# HRT_D_ER100_V1_0.net
KiCad netlist of a schematic drawn in Altium Designer
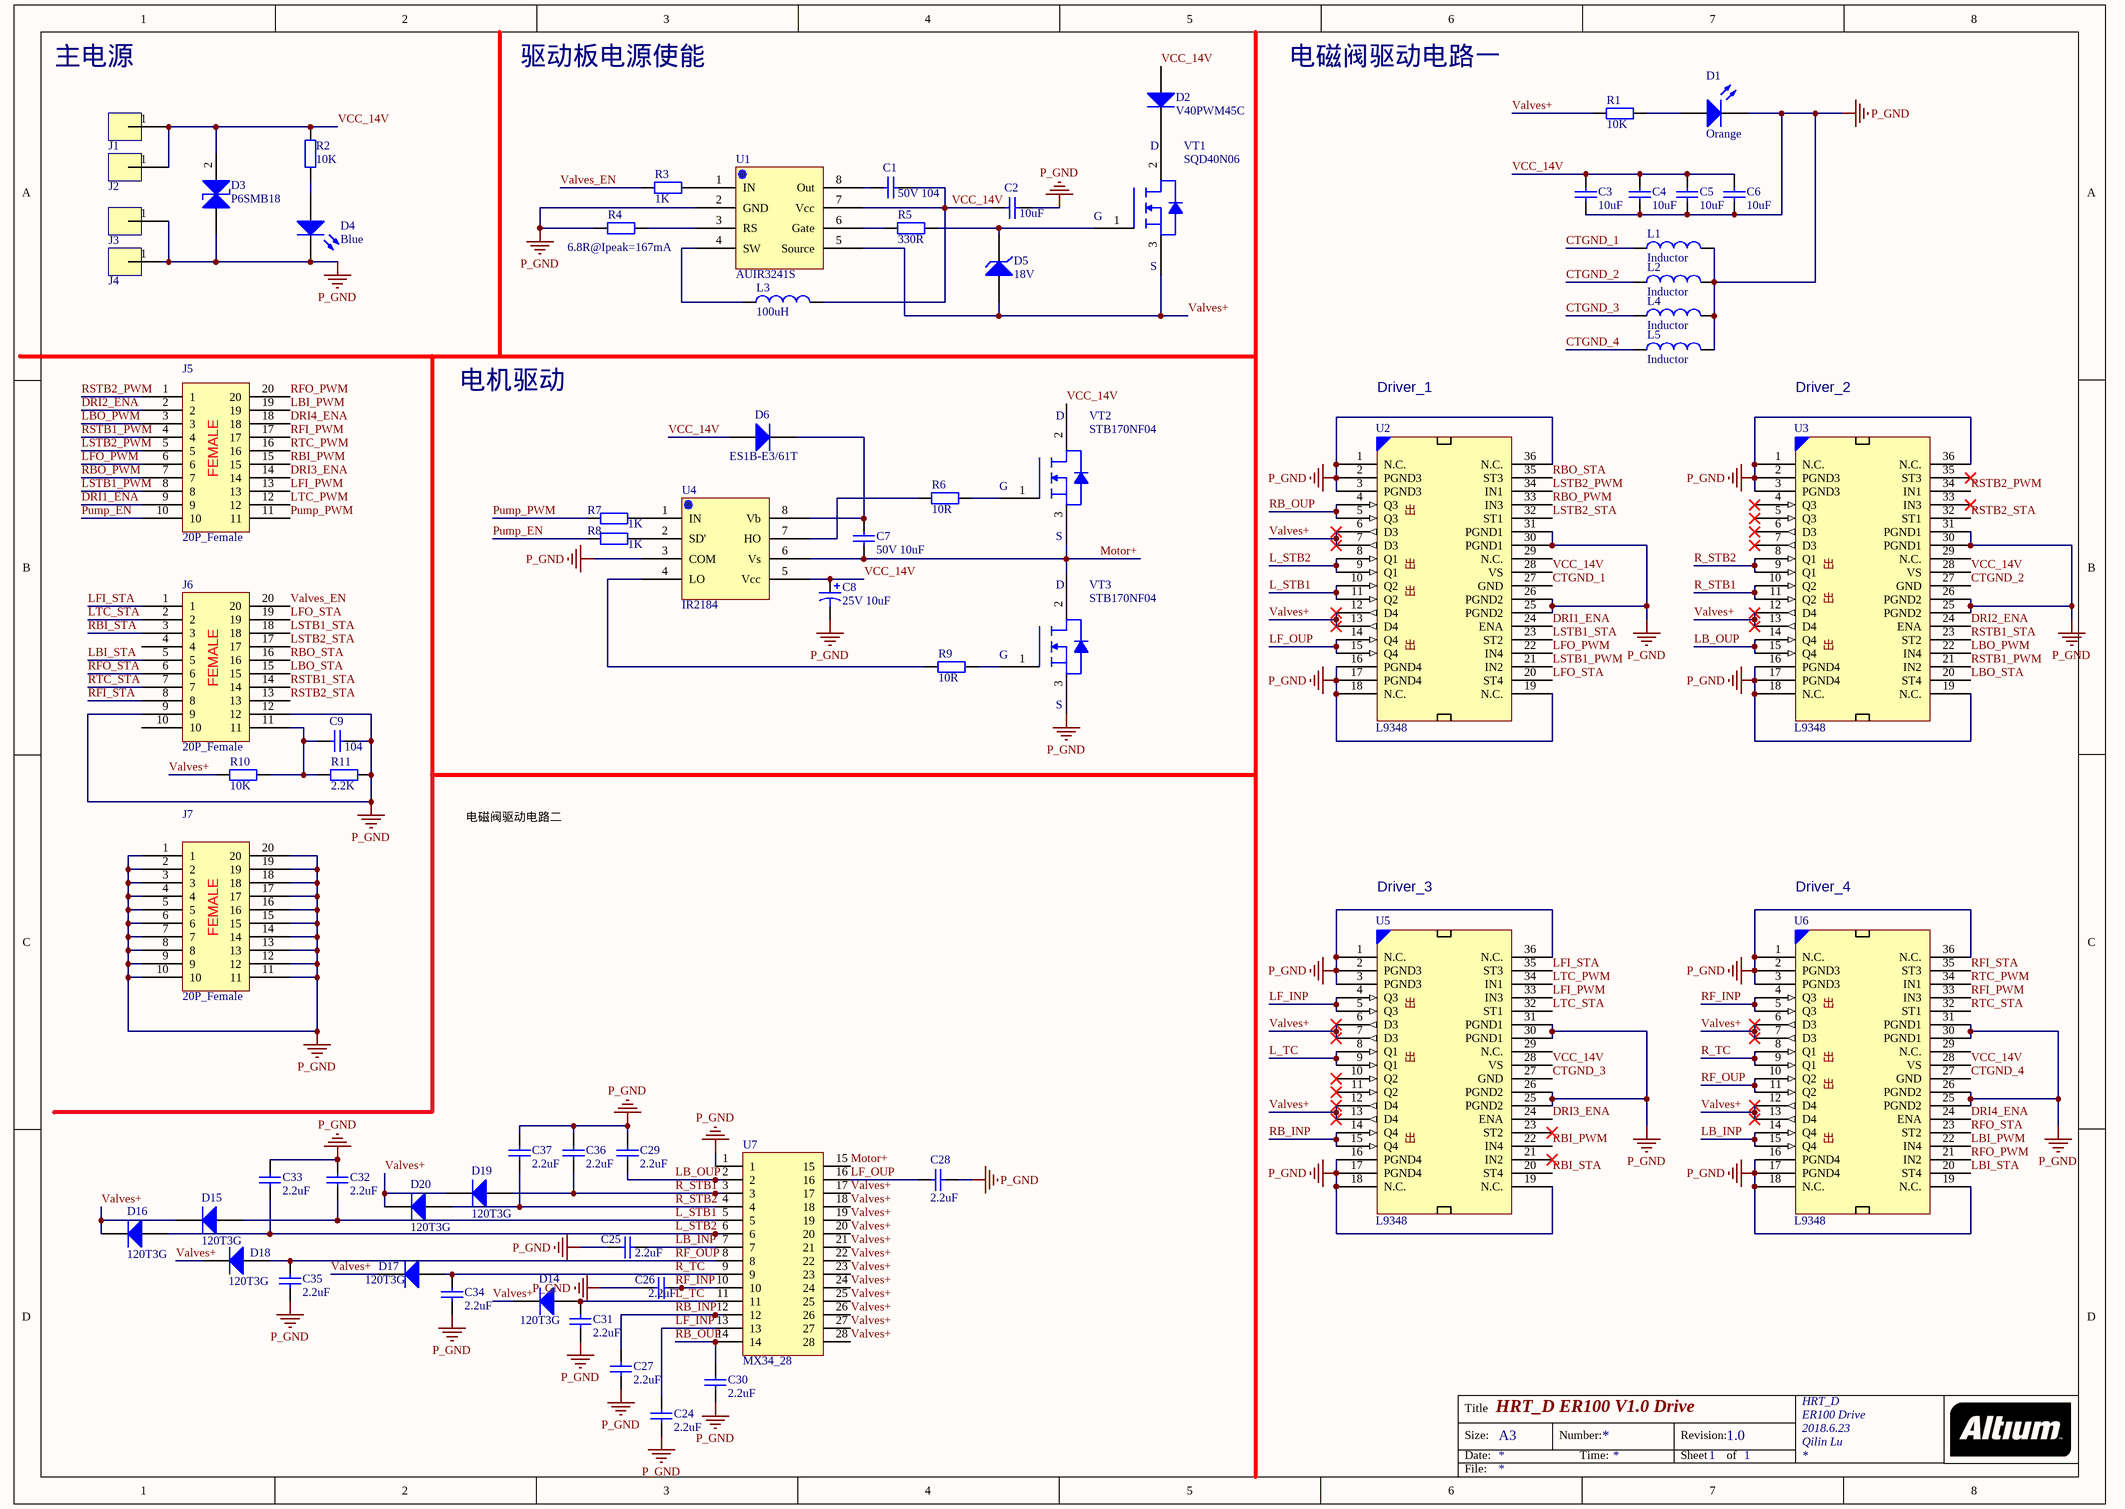
[diagram p0: HRT_D ER100 V1.0.SchDoc]

(export (version "E")
  (design (tool "Eeschema 10.0.6"))
  (components
    (comp (ref "C1")
      (value "50V 104")
      (footprint "C 0805")
      (description "无极性电容")
      (libsource (lib "HRT_D Integrated_Library") (part "Cap"))
    )
    (comp (ref "C2")
      (value "10uF")
      (footprint "C 0805")
      (description "无极性电容")
      (libsource (lib "HRT_D Integrated_Library") (part "Cap"))
    )
    (comp (ref "C3")
      (value "10uF")
      (footprint "C 0805")
      (description "无极性电容")
      (libsource (lib "HRT_D Integrated_Library") (part "Cap"))
    )
    (comp (ref "C4")
      (value "10uF")
      (footprint "C 0805")
      (description "无极性电容")
      (libsource (lib "HRT_D Integrated_Library") (part "Cap"))
    )
    (comp (ref "C5")
      (value "10uF")
      (footprint "C 0805")
      (description "无极性电容")
      (libsource (lib "HRT_D Integrated_Library") (part "Cap"))
    )
    (comp (ref "C6")
      (value "10uF")
      (footprint "C 0805")
      (description "无极性电容")
      (libsource (lib "HRT_D Integrated_Library") (part "Cap"))
    )
    (comp (ref "C7")
      (value "50V 10uF")
      (footprint "C 0805")
      (description "无极性电容")
      (libsource (lib "HRT_D Integrated_Library") (part "Cap"))
    )
    (comp (ref "C8")
      (value "25V 10uF")
      (footprint "CP 3528B")
      (description "极性电容")
      (libsource (lib "HRT_D Integrated_Library") (part "Cap_Pol"))
    )
    (comp (ref "C9")
      (value "104")
      (footprint "C 0805")
      (description "无极性电容")
      (libsource (lib "HRT_D Integrated_Library") (part "Cap"))
    )
    (comp (ref "C24")
      (value "2.2uF")
      (footprint "C 0805")
      (description "无极性电容")
      (libsource (lib "ER100_ESC") (part "Cap"))
    )
    (comp (ref "C25")
      (value "2.2uF")
      (footprint "C 0805")
      (description "无极性电容")
      (libsource (lib "ER100_ESC") (part "Cap"))
    )
    (comp (ref "C26")
      (value "2.2uF")
      (footprint "C 0805")
      (description "无极性电容")
      (libsource (lib "ER100_ESC") (part "Cap"))
    )
    (comp (ref "C27")
      (value "2.2uF")
      (footprint "C 0805")
      (description "无极性电容")
      (libsource (lib "ER100_ESC") (part "Cap"))
    )
    (comp (ref "C28")
      (value "2.2uF")
      (footprint "C 0805")
      (description "无极性电容")
      (libsource (lib "ER100_ESC") (part "Cap"))
    )
    (comp (ref "C29")
      (value "2.2uF")
      (footprint "C 0805")
      (description "无极性电容")
      (libsource (lib "ER100_ESC") (part "Cap"))
    )
    (comp (ref "C30")
      (value "2.2uF")
      (footprint "C 0805")
      (description "无极性电容")
      (libsource (lib "ER100_ESC") (part "Cap"))
    )
    (comp (ref "C31")
      (value "2.2uF")
      (footprint "C 0805")
      (description "无极性电容")
      (libsource (lib "ER100_ESC") (part "Cap"))
    )
    (comp (ref "C32")
      (value "2.2uF")
      (footprint "C 0805")
      (description "无极性电容")
      (libsource (lib "ER100_ESC") (part "Cap"))
    )
    (comp (ref "C33")
      (value "2.2uF")
      (footprint "C 0805")
      (description "无极性电容")
      (libsource (lib "ER100_ESC") (part "Cap"))
    )
    (comp (ref "C34")
      (value "2.2uF")
      (footprint "C 0805")
      (description "无极性电容")
      (libsource (lib "ER100_ESC") (part "Cap"))
    )
    (comp (ref "C35")
      (value "2.2uF")
      (footprint "C 0805")
      (description "无极性电容")
      (libsource (lib "ER100_ESC") (part "Cap"))
    )
    (comp (ref "C36")
      (value "2.2uF")
      (footprint "C 0805")
      (description "无极性电容")
      (libsource (lib "ER100_ESC") (part "Cap"))
    )
    (comp (ref "C37")
      (value "2.2uF")
      (footprint "C 0805")
      (description "无极性电容")
      (libsource (lib "ER100_ESC") (part "Cap"))
    )
    (comp (ref "D1")
      (value "Orange")
      (footprint "LED_0805")
      (description "发光二极管")
      (libsource (lib "HRT_D Integrated_Library") (part "LED"))
    )
    (comp (ref "D2")
      (value "V40PWM45C")
      (footprint "TO252_DIO")
      (description "二极管")
      (libsource (lib "HRT_D Integrated_Library") (part "Diode"))
    )
    (comp (ref "D3")
      (value "P6SMB18")
      (footprint "DO-214AA")
      (description "BiDir TVS Diode")
      (libsource (lib "HRT_D Integrated_Library") (part "P6SMBXX"))
    )
    (comp (ref "D4")
      (value "Blue")
      (footprint "LED_0805")
      (description "发光二极管")
      (libsource (lib "HRT_D Integrated_Library") (part "LED"))
    )
    (comp (ref "D5")
      (value "18V")
      (footprint "LL34")
      (libsource (lib "HRT_D Integrated_Library") (part "Diode_Zener"))
    )
    (comp (ref "D6")
      (value "ES1B-E3/61T")
      (footprint "DO-214AC")
      (description "二极管")
      (libsource (lib "HRT_D Integrated_Library") (part "Diode"))
    )
    (comp (ref "D14")
      (value "120T3G")
      (footprint "DO-214")
      (description "二极管")
      (libsource (lib "ER100_ESC") (part "Diode"))
    )
    (comp (ref "D15")
      (value "120T3G")
      (footprint "DO-214")
      (description "二极管")
      (libsource (lib "ER100_ESC") (part "Diode"))
    )
    (comp (ref "D16")
      (value "120T3G")
      (footprint "DO-214")
      (description "二极管")
      (libsource (lib "ER100_ESC") (part "Diode"))
    )
    (comp (ref "D17")
      (value "120T3G")
      (footprint "DO-214")
      (description "二极管")
      (libsource (lib "ER100_ESC") (part "Diode"))
    )
    (comp (ref "D18")
      (value "120T3G")
      (footprint "DO-214")
      (description "二极管")
      (libsource (lib "ER100_ESC") (part "Diode"))
    )
    (comp (ref "D19")
      (value "120T3G")
      (footprint "DO-214")
      (description "二极管")
      (libsource (lib "ER100_ESC") (part "Diode"))
    )
    (comp (ref "D20")
      (value "120T3G")
      (footprint "DO-214")
      (description "二极管")
      (libsource (lib "ER100_ESC") (part "Diode"))
    )
    (comp (ref "J1")
      (value "SMT_Connector")
      (footprint "SMT_Connector")
      (description "表贴接线端")
      (libsource (lib "HRT_D Integrated_Library") (part "SMT_Connector"))
    )
    (comp (ref "J2")
      (value "SMT_Connector")
      (footprint "SMT_Connector")
      (description "表贴接线端")
      (libsource (lib "HRT_D Integrated_Library") (part "SMT_Connector"))
    )
    (comp (ref "J3")
      (value "SMT_Connector")
      (footprint "SMT_Connector")
      (description "表贴接线端")
      (libsource (lib "HRT_D Integrated_Library") (part "SMT_Connector"))
    )
    (comp (ref "J4")
      (value "SMT_Connector")
      (footprint "SMT_Connector")
      (description "表贴接线端")
      (libsource (lib "HRT_D Integrated_Library") (part "SMT_Connector"))
    )
    (comp (ref "J5")
      (value "20P_Female")
      (footprint "B2B_1.27_Female")
      (description "板对板连接器 母头")
      (libsource (lib "HRT_D Integrated_Library") (part "B2B_1.27_Female"))
    )
    (comp (ref "J6")
      (value "20P_Female")
      (footprint "B2B_1.27_Female")
      (description "板对板连接器 母头")
      (libsource (lib "HRT_D Integrated_Library") (part "B2B_1.27_Female"))
    )
    (comp (ref "J7")
      (value "20P_Female")
      (footprint "B2B_1.27_Female")
      (description "板对板连接器 母头")
      (libsource (lib "HRT_D Integrated_Library") (part "B2B_1.27_Female"))
    )
    (comp (ref "L1")
      (value "Inductor")
      (footprint "L 0805")
      (description "电感")
      (libsource (lib "HRT_D Integrated_Library") (part "Inductor"))
    )
    (comp (ref "L2")
      (value "Inductor")
      (footprint "L 0805")
      (description "电感")
      (libsource (lib "HRT_D Integrated_Library") (part "Inductor"))
    )
    (comp (ref "L3")
      (value "100uH")
      (footprint "L 1812")
      (description "电感")
      (libsource (lib "HRT_D Integrated_Library") (part "Inductor"))
    )
    (comp (ref "L4")
      (value "Inductor")
      (footprint "L 0805")
      (description "电感")
      (libsource (lib "HRT_D Integrated_Library") (part "Inductor"))
    )
    (comp (ref "L5")
      (value "Inductor")
      (footprint "L 0805")
      (description "电感")
      (libsource (lib "HRT_D Integrated_Library") (part "Inductor"))
    )
    (comp (ref "R1")
      (value "10K")
      (footprint "R 0603")
      (description "电阻")
      (libsource (lib "HRT_D Integrated_Library") (part "Resistor"))
    )
    (comp (ref "R2")
      (value "10K")
      (footprint "R 0603")
      (description "电阻")
      (libsource (lib "") (part "Resistor_2"))
    )
    (comp (ref "R3")
      (value "1K")
      (footprint "R 0603")
      (description "电阻")
      (libsource (lib "HRT_D Integrated_Library") (part "Resistor"))
    )
    (comp (ref "R4")
      (value "6.8R@Ipeak=167mA")
      (footprint "R 0805")
      (description "电阻")
      (libsource (lib "HRT_D Integrated_Library") (part "Resistor"))
    )
    (comp (ref "R5")
      (value "330R")
      (footprint "R 0805")
      (description "电阻")
      (libsource (lib "HRT_D Integrated_Library") (part "Resistor"))
    )
    (comp (ref "R6")
      (value "10R")
      (footprint "R 0805")
      (description "电阻")
      (libsource (lib "HRT_D Integrated_Library") (part "Resistor"))
    )
    (comp (ref "R7")
      (value "1K")
      (footprint "R 0603")
      (description "电阻")
      (libsource (lib "HRT_D Integrated_Library") (part "Resistor"))
    )
    (comp (ref "R8")
      (value "1K")
      (footprint "R 0603")
      (description "电阻")
      (libsource (lib "HRT_D Integrated_Library") (part "Resistor"))
    )
    (comp (ref "R9")
      (value "10R")
      (footprint "R 0805")
      (description "电阻")
      (libsource (lib "HRT_D Integrated_Library") (part "Resistor"))
    )
    (comp (ref "R10")
      (value "10K")
      (footprint "R 0805")
      (description "电阻")
      (libsource (lib "") (part "Resistor_1"))
    )
    (comp (ref "R11")
      (value "2.2K")
      (footprint "R 0805")
      (description "电阻")
      (libsource (lib "HRT_D Integrated_Library") (part "Resistor"))
    )
    (comp (ref "U1")
      (value "AUIR3241S")
      (footprint "SOP8")
      (description "B2B MOSFET Driver")
      (libsource (lib "HRT_D Integrated_Library") (part "AUIR3241S"))
    )
    (comp (ref "U2")
      (value "L9348")
      (footprint "PowerSO-36")
      (description "4路电磁阀驱动")
      (libsource (lib "HRT_D Integrated_Library") (part "L9348"))
    )
    (comp (ref "U3")
      (value "L9348")
      (footprint "PowerSO-36")
      (description "4路电磁阀驱动")
      (libsource (lib "HRT_D Integrated_Library") (part "L9348"))
    )
    (comp (ref "U4")
      (value "IR2184")
      (footprint "SOP8")
      (description "Half-Bridge Gate Driver")
      (libsource (lib "HRT_D Integrated_Library") (part "IR2184"))
    )
    (comp (ref "U5")
      (value "L9348")
      (footprint "PowerSO-36")
      (description "4路电磁阀驱动")
      (libsource (lib "HRT_D Integrated_Library") (part "L9348"))
    )
    (comp (ref "U6")
      (value "L9348")
      (footprint "PowerSO-36")
      (description "4路电磁阀驱动")
      (libsource (lib "HRT_D Integrated_Library") (part "L9348"))
    )
    (comp (ref "U7")
      (value "MX34_28")
      (footprint "mx34_28")
      (libsource (lib "HRT_D Schlib") (part "MX34_28"))
    )
    (comp (ref "VT1")
      (value "SQD40N06")
      (footprint "TO252")
      (libsource (lib "HRT_D Integrated_Library") (part "PowerMos_N"))
    )
    (comp (ref "VT2")
      (value "STB170NF04")
      (footprint "TO263-3B")
      (libsource (lib "HRT_D Integrated_Library") (part "PowerMos_N"))
    )
    (comp (ref "VT3")
      (value "STB170NF04")
      (footprint "TO263-3B")
      (libsource (lib "HRT_D Integrated_Library") (part "PowerMos_N"))
    )
  )
  (nets
    (net (code "1") (name "/CTGND_1") (class "Default")
      (node (ref "L1") (pin "1") (pinfunction "1_1") (pintype "passive"))
      (node (ref "U2") (pin "27") (pinfunction "GND_27") (pintype "passive"))
    )
    (net (code "2") (name "/CTGND_2") (class "Default")
      (node (ref "L2") (pin "1") (pinfunction "1_1") (pintype "passive"))
      (node (ref "U3") (pin "27") (pinfunction "GND_27") (pintype "passive"))
    )
    (net (code "3") (name "/CTGND_3") (class "Default")
      (node (ref "L4") (pin "1") (pinfunction "1_1") (pintype "passive"))
      (node (ref "U5") (pin "27") (pinfunction "GND_27") (pintype "passive"))
    )
    (net (code "4") (name "/CTGND_4") (class "Default")
      (node (ref "L5") (pin "1") (pinfunction "1_1") (pintype "passive"))
      (node (ref "U6") (pin "27") (pinfunction "GND_27") (pintype "passive"))
    )
    (net (code "5") (name "/DRI1_ENA") (class "Default")
      (node (ref "J5") (pin "9") (pinfunction "9_9") (pintype "passive"))
      (node (ref "U2") (pin "24") (pinfunction "ENA_24") (pintype "passive"))
    )
    (net (code "6") (name "/DRI2_ENA") (class "Default")
      (node (ref "J5") (pin "2") (pinfunction "2_2") (pintype "passive"))
      (node (ref "U3") (pin "24") (pinfunction "ENA_24") (pintype "passive"))
    )
    (net (code "7") (name "/DRI3_ENA") (class "Default")
      (node (ref "J5") (pin "14") (pinfunction "14_14") (pintype "passive"))
      (node (ref "U5") (pin "24") (pinfunction "ENA_24") (pintype "passive"))
    )
    (net (code "8") (name "/DRI4_ENA") (class "Default")
      (node (ref "J5") (pin "18") (pinfunction "18_18") (pintype "passive"))
      (node (ref "U6") (pin "24") (pinfunction "ENA_24") (pintype "passive"))
    )
    (net (code "9") (name "/LBI_PWM") (class "Default")
      (node (ref "J5") (pin "19") (pinfunction "19_19") (pintype "passive"))
      (node (ref "U6") (pin "22") (pinfunction "IN4_22") (pintype "passive"))
    )
    (net (code "10") (name "/LBI_STA") (class "Default")
      (node (ref "J6") (pin "5") (pinfunction "5_5") (pintype "passive"))
      (node (ref "U6") (pin "20") (pinfunction "ST4_20") (pintype "passive"))
    )
    (net (code "11") (name "/LBO_PWM") (class "Default")
      (node (ref "J5") (pin "3") (pinfunction "3_3") (pintype "passive"))
      (node (ref "U3") (pin "22") (pinfunction "IN4_22") (pintype "passive"))
    )
    (net (code "12") (name "/LBO_STA") (class "Default")
      (node (ref "J6") (pin "15") (pinfunction "15_15") (pintype "passive"))
      (node (ref "U3") (pin "20") (pinfunction "ST4_20") (pintype "passive"))
    )
    (net (code "13") (name "/LB_INP") (class "Default")
      (node (ref "C25") (pin "2") (pinfunction "2_2") (pintype "passive"))
      (node (ref "U6") (pin "14") (pinfunction "Q4_14") (pintype "input"))
      (node (ref "U6") (pin "15") (pinfunction "Q4_15") (pintype "input"))
      (node (ref "U7") (pin "7") (pinfunction "7_7") (pintype "passive"))
    )
    (net (code "14") (name "/LB_OUP") (class "Default")
      (node (ref "C29") (pin "2") (pinfunction "2_2") (pintype "passive"))
      (node (ref "U3") (pin "14") (pinfunction "Q4_14") (pintype "input"))
      (node (ref "U3") (pin "15") (pinfunction "Q4_15") (pintype "input"))
      (node (ref "U7") (pin "2") (pinfunction "2_2") (pintype "passive"))
    )
    (net (code "15") (name "/LFI_PWM") (class "Default")
      (node (ref "J5") (pin "13") (pinfunction "13_13") (pintype "passive"))
      (node (ref "U5") (pin "33") (pinfunction "IN3_33") (pintype "passive"))
    )
    (net (code "16") (name "/LFI_STA") (class "Default")
      (node (ref "J6") (pin "1") (pinfunction "1_1") (pintype "passive"))
      (node (ref "U5") (pin "35") (pinfunction "ST3_35") (pintype "passive"))
    )
    (net (code "17") (name "/LFO_PWM") (class "Default")
      (node (ref "J5") (pin "6") (pinfunction "6_6") (pintype "passive"))
      (node (ref "U2") (pin "22") (pinfunction "IN4_22") (pintype "passive"))
    )
    (net (code "18") (name "/LFO_STA") (class "Default")
      (node (ref "J6") (pin "19") (pinfunction "19_19") (pintype "passive"))
      (node (ref "U2") (pin "20") (pinfunction "ST4_20") (pintype "passive"))
    )
    (net (code "19") (name "/LF_INP") (class "Default")
      (node (ref "C24") (pin "1") (pinfunction "1_1") (pintype "passive"))
      (node (ref "U5") (pin "4") (pinfunction "Q3_4") (pintype "input"))
      (node (ref "U5") (pin "5") (pinfunction "Q3_5") (pintype "input"))
      (node (ref "U7") (pin "13") (pinfunction "13_13") (pintype "passive"))
    )
    (net (code "20") (name "/LF_OUP") (class "Default")
      (node (ref "C28") (pin "2") (pinfunction "2_2") (pintype "passive"))
      (node (ref "U2") (pin "14") (pinfunction "Q4_14") (pintype "input"))
      (node (ref "U2") (pin "15") (pinfunction "Q4_15") (pintype "input"))
      (node (ref "U7") (pin "16") (pinfunction "16_16") (pintype "passive"))
    )
    (net (code "21") (name "/LSTB1_PWM") (class "Default")
      (node (ref "J5") (pin "8") (pinfunction "8_8") (pintype "passive"))
      (node (ref "U2") (pin "21") (pinfunction "IN2_21") (pintype "passive"))
    )
    (net (code "22") (name "/LSTB1_STA") (class "Default")
      (node (ref "J6") (pin "18") (pinfunction "18_18") (pintype "passive"))
      (node (ref "U2") (pin "23") (pinfunction "ST2_23") (pintype "passive"))
    )
    (net (code "23") (name "/LSTB2_PWM") (class "Default")
      (node (ref "J5") (pin "5") (pinfunction "5_5") (pintype "passive"))
      (node (ref "U2") (pin "34") (pinfunction "IN1_34") (pintype "passive"))
    )
    (net (code "24") (name "/LSTB2_STA") (class "Default")
      (node (ref "J6") (pin "17") (pinfunction "17_17") (pintype "passive"))
      (node (ref "U2") (pin "32") (pinfunction "ST1_32") (pintype "passive"))
    )
    (net (code "25") (name "/LTC_PWM") (class "Default")
      (node (ref "J5") (pin "12") (pinfunction "12_12") (pintype "passive"))
      (node (ref "U5") (pin "34") (pinfunction "IN1_34") (pintype "passive"))
    )
    (net (code "26") (name "/LTC_STA") (class "Default")
      (node (ref "J6") (pin "2") (pinfunction "2_2") (pintype "passive"))
      (node (ref "U5") (pin "32") (pinfunction "ST1_32") (pintype "passive"))
    )
    (net (code "27") (name "/L_STB1") (class "Default")
      (node (ref "C32") (pin "1") (pinfunction "1_1") (pintype "passive"))
      (node (ref "D15") (pin "1") (pinfunction "A_1") (pintype "passive"))
      (node (ref "U2") (pin "10") (pinfunction "Q2_10") (pintype "input"))
      (node (ref "U2") (pin "11") (pinfunction "Q2_11") (pintype "input"))
      (node (ref "U7") (pin "5") (pinfunction "5_5") (pintype "passive"))
    )
    (net (code "28") (name "/L_STB2") (class "Default")
      (node (ref "C33") (pin "1") (pinfunction "1_1") (pintype "passive"))
      (node (ref "D16") (pin "1") (pinfunction "A_1") (pintype "passive"))
      (node (ref "U2") (pin "8") (pinfunction "Q1_8") (pintype "input"))
      (node (ref "U2") (pin "9") (pinfunction "Q1_9") (pintype "input"))
      (node (ref "U7") (pin "6") (pinfunction "6_6") (pintype "passive"))
    )
    (net (code "29") (name "/L_TC") (class "Default")
      (node (ref "C31") (pin "2") (pinfunction "2_2") (pintype "passive"))
      (node (ref "D14") (pin "1") (pinfunction "A_1") (pintype "passive"))
      (node (ref "U5") (pin "8") (pinfunction "Q1_8") (pintype "input"))
      (node (ref "U5") (pin "9") (pinfunction "Q1_9") (pintype "input"))
      (node (ref "U7") (pin "11") (pinfunction "11_11") (pintype "passive"))
    )
    (net (code "30") (name "/Motor+") (class "Default")
      (node (ref "C7") (pin "2") (pinfunction "2_2") (pintype "passive"))
      (node (ref "U4") (pin "6") (pinfunction "Vs_6") (pintype "passive"))
      (node (ref "U7") (pin "15") (pinfunction "15_15") (pintype "passive"))
      (node (ref "VT2") (pin "3") (pinfunction "3_3") (pintype "passive"))
      (node (ref "VT3") (pin "2") (pinfunction "2_2") (pintype "passive"))
    )
    (net (code "31") (name "/Pump_EN") (class "Default")
      (node (ref "J5") (pin "10") (pinfunction "10_10") (pintype "passive"))
      (node (ref "R8") (pin "1") (pinfunction "1_1") (pintype "passive"))
    )
    (net (code "32") (name "/Pump_PWM") (class "Default")
      (node (ref "J5") (pin "11") (pinfunction "11_11") (pintype "passive"))
      (node (ref "R7") (pin "1") (pinfunction "1_1") (pintype "passive"))
    )
    (net (code "33") (name "/RBI_PWM") (class "Default")
      (node (ref "J5") (pin "15") (pinfunction "15_15") (pintype "passive"))
      (node (ref "U5") (pin "22") (pinfunction "IN4_22") (pintype "passive"))
    )
    (net (code "34") (name "/RBI_STA") (class "Default")
      (node (ref "J6") (pin "3") (pinfunction "3_3") (pintype "passive"))
      (node (ref "U5") (pin "20") (pinfunction "ST4_20") (pintype "passive"))
    )
    (net (code "35") (name "/RBO_PWM") (class "Default")
      (node (ref "J5") (pin "7") (pinfunction "7_7") (pintype "passive"))
      (node (ref "U2") (pin "33") (pinfunction "IN3_33") (pintype "passive"))
    )
    (net (code "36") (name "/RBO_STA") (class "Default")
      (node (ref "J6") (pin "16") (pinfunction "16_16") (pintype "passive"))
      (node (ref "U2") (pin "35") (pinfunction "ST3_35") (pintype "passive"))
    )
    (net (code "37") (name "/RB_INP") (class "Default")
      (node (ref "C27") (pin "2") (pinfunction "2_2") (pintype "passive"))
      (node (ref "U5") (pin "14") (pinfunction "Q4_14") (pintype "input"))
      (node (ref "U5") (pin "15") (pinfunction "Q4_15") (pintype "input"))
      (node (ref "U7") (pin "12") (pinfunction "12_12") (pintype "passive"))
    )
    (net (code "38") (name "/RB_OUP") (class "Default")
      (node (ref "C30") (pin "2") (pinfunction "2_2") (pintype "passive"))
      (node (ref "U2") (pin "4") (pinfunction "Q3_4") (pintype "input"))
      (node (ref "U2") (pin "5") (pinfunction "Q3_5") (pintype "input"))
      (node (ref "U7") (pin "14") (pinfunction "14_14") (pintype "passive"))
    )
    (net (code "39") (name "/RFI_PWM") (class "Default")
      (node (ref "J5") (pin "17") (pinfunction "17_17") (pintype "passive"))
      (node (ref "U6") (pin "33") (pinfunction "IN3_33") (pintype "passive"))
    )
    (net (code "40") (name "/RFI_STA") (class "Default")
      (node (ref "J6") (pin "8") (pinfunction "8_8") (pintype "passive"))
      (node (ref "U6") (pin "35") (pinfunction "ST3_35") (pintype "passive"))
    )
    (net (code "41") (name "/RFO_PWM") (class "Default")
      (node (ref "J5") (pin "20") (pinfunction "20_20") (pintype "passive"))
      (node (ref "U6") (pin "21") (pinfunction "IN2_21") (pintype "passive"))
    )
    (net (code "42") (name "/RFO_STA") (class "Default")
      (node (ref "J6") (pin "6") (pinfunction "6_6") (pintype "passive"))
      (node (ref "U6") (pin "23") (pinfunction "ST2_23") (pintype "passive"))
    )
    (net (code "43") (name "/RF_INP") (class "Default")
      (node (ref "C26") (pin "2") (pinfunction "2_2") (pintype "passive"))
      (node (ref "U6") (pin "4") (pinfunction "Q3_4") (pintype "input"))
      (node (ref "U6") (pin "5") (pinfunction "Q3_5") (pintype "input"))
      (node (ref "U7") (pin "10") (pinfunction "10_10") (pintype "passive"))
    )
    (net (code "44") (name "/RF_OUP") (class "Default")
      (node (ref "C35") (pin "1") (pinfunction "1_1") (pintype "passive"))
      (node (ref "D18") (pin "1") (pinfunction "A_1") (pintype "passive"))
      (node (ref "U6") (pin "10") (pinfunction "Q2_10") (pintype "input"))
      (node (ref "U6") (pin "11") (pinfunction "Q2_11") (pintype "input"))
      (node (ref "U7") (pin "8") (pinfunction "8_8") (pintype "passive"))
    )
    (net (code "45") (name "/RSTB1_PWM") (class "Default")
      (node (ref "J5") (pin "4") (pinfunction "4_4") (pintype "passive"))
      (node (ref "U3") (pin "21") (pinfunction "IN2_21") (pintype "passive"))
    )
    (net (code "46") (name "/RSTB1_STA") (class "Default")
      (node (ref "J6") (pin "14") (pinfunction "14_14") (pintype "passive"))
      (node (ref "U3") (pin "23") (pinfunction "ST2_23") (pintype "passive"))
    )
    (net (code "47") (name "/RSTB2_PWM") (class "Default")
      (node (ref "J5") (pin "1") (pinfunction "1_1") (pintype "passive"))
      (node (ref "U3") (pin "34") (pinfunction "IN1_34") (pintype "passive"))
    )
    (net (code "48") (name "/RSTB2_STA") (class "Default")
      (node (ref "J6") (pin "13") (pinfunction "13_13") (pintype "passive"))
      (node (ref "U3") (pin "32") (pinfunction "ST1_32") (pintype "passive"))
    )
    (net (code "49") (name "/RTC_PWM") (class "Default")
      (node (ref "J5") (pin "16") (pinfunction "16_16") (pintype "passive"))
      (node (ref "U6") (pin "34") (pinfunction "IN1_34") (pintype "passive"))
    )
    (net (code "50") (name "/RTC_STA") (class "Default")
      (node (ref "J6") (pin "7") (pinfunction "7_7") (pintype "passive"))
      (node (ref "U6") (pin "32") (pinfunction "ST1_32") (pintype "passive"))
    )
    (net (code "51") (name "/R_STB1") (class "Default")
      (node (ref "C36") (pin "2") (pinfunction "2_2") (pintype "passive"))
      (node (ref "D19") (pin "1") (pinfunction "A_1") (pintype "passive"))
      (node (ref "U3") (pin "10") (pinfunction "Q2_10") (pintype "input"))
      (node (ref "U3") (pin "11") (pinfunction "Q2_11") (pintype "input"))
      (node (ref "U7") (pin "3") (pinfunction "3_3") (pintype "passive"))
    )
    (net (code "52") (name "/R_STB2") (class "Default")
      (node (ref "C37") (pin "2") (pinfunction "2_2") (pintype "passive"))
      (node (ref "D20") (pin "1") (pinfunction "A_1") (pintype "passive"))
      (node (ref "U3") (pin "8") (pinfunction "Q1_8") (pintype "input"))
      (node (ref "U3") (pin "9") (pinfunction "Q1_9") (pintype "input"))
      (node (ref "U7") (pin "4") (pinfunction "4_4") (pintype "passive"))
    )
    (net (code "53") (name "/R_TC") (class "Default")
      (node (ref "C34") (pin "2") (pinfunction "2_2") (pintype "passive"))
      (node (ref "D17") (pin "1") (pinfunction "A_1") (pintype "passive"))
      (node (ref "U6") (pin "8") (pinfunction "Q1_8") (pintype "input"))
      (node (ref "U6") (pin "9") (pinfunction "Q1_9") (pintype "input"))
      (node (ref "U7") (pin "9") (pinfunction "9_9") (pintype "passive"))
    )
    (net (code "54") (name "/VCC_14V") (class "Default")
      (node (ref "C1") (pin "2") (pinfunction "2_2") (pintype "passive"))
      (node (ref "C2") (pin "2") (pinfunction "2_2") (pintype "passive"))
      (node (ref "C3") (pin "1") (pinfunction "1_1") (pintype "passive"))
      (node (ref "C4") (pin "1") (pinfunction "1_1") (pintype "passive"))
      (node (ref "C5") (pin "1") (pinfunction "1_1") (pintype "passive"))
      (node (ref "C6") (pin "1") (pinfunction "1_1") (pintype "passive"))
      (node (ref "C8") (pin "1") (pinfunction "1_1") (pintype "passive"))
      (node (ref "D2") (pin "1") (pinfunction "A_1") (pintype "passive"))
      (node (ref "D3") (pin "2") (pinfunction "K_2") (pintype "passive"))
      (node (ref "D6") (pin "1") (pinfunction "A_1") (pintype "passive"))
      (node (ref "J1") (pin "1") (pinfunction "1_1") (pintype "passive"))
      (node (ref "J2") (pin "1") (pinfunction "1_1") (pintype "passive"))
      (node (ref "L3") (pin "2") (pinfunction "2_2") (pintype "passive"))
      (node (ref "R2") (pin "2") (pinfunction "2_2") (pintype "passive"))
      (node (ref "U1") (pin "7") (pinfunction "Vcc_7") (pintype "passive"))
      (node (ref "U2") (pin "28") (pinfunction "VS_28") (pintype "passive"))
      (node (ref "U3") (pin "28") (pinfunction "VS_28") (pintype "passive"))
      (node (ref "U4") (pin "5") (pinfunction "Vcc_5") (pintype "passive"))
      (node (ref "U5") (pin "28") (pinfunction "VS_28") (pintype "passive"))
      (node (ref "U6") (pin "28") (pinfunction "VS_28") (pintype "passive"))
      (node (ref "VT2") (pin "2") (pinfunction "2_2") (pintype "passive"))
    )
    (net (code "55") (name "/Valves+") (class "Default")
      (node (ref "D14") (pin "2") (pinfunction "K_2") (pintype "passive"))
      (node (ref "D15") (pin "2") (pinfunction "K_2") (pintype "passive"))
      (node (ref "D16") (pin "2") (pinfunction "K_2") (pintype "passive"))
      (node (ref "D17") (pin "2") (pinfunction "K_2") (pintype "passive"))
      (node (ref "D18") (pin "2") (pinfunction "K_2") (pintype "passive"))
      (node (ref "D19") (pin "2") (pinfunction "K_2") (pintype "passive"))
      (node (ref "D20") (pin "2") (pinfunction "K_2") (pintype "passive"))
      (node (ref "D5") (pin "1") (pinfunction "A_1") (pintype "passive"))
      (node (ref "R1") (pin "1") (pinfunction "1_1") (pintype "passive"))
      (node (ref "R10") (pin "2") (pinfunction "2_2") (pintype "passive"))
      (node (ref "U1") (pin "5") (pinfunction "Source_5") (pintype "passive"))
      (node (ref "U2") (pin "12") (pinfunction "D4_12") (pintype "output"))
      (node (ref "U2") (pin "13") (pinfunction "D4_13") (pintype "output"))
      (node (ref "U2") (pin "6") (pinfunction "D3_6") (pintype "output"))
      (node (ref "U2") (pin "7") (pinfunction "D3_7") (pintype "output"))
      (node (ref "U3") (pin "12") (pinfunction "D4_12") (pintype "output"))
      (node (ref "U3") (pin "13") (pinfunction "D4_13") (pintype "output"))
      (node (ref "U5") (pin "12") (pinfunction "D4_12") (pintype "output"))
      (node (ref "U5") (pin "13") (pinfunction "D4_13") (pintype "output"))
      (node (ref "U5") (pin "6") (pinfunction "D3_6") (pintype "output"))
      (node (ref "U5") (pin "7") (pinfunction "D3_7") (pintype "output"))
      (node (ref "U6") (pin "12") (pinfunction "D4_12") (pintype "output"))
      (node (ref "U6") (pin "13") (pinfunction "D4_13") (pintype "output"))
      (node (ref "U6") (pin "6") (pinfunction "D3_6") (pintype "output"))
      (node (ref "U6") (pin "7") (pinfunction "D3_7") (pintype "output"))
      (node (ref "U7") (pin "17") (pinfunction "17_17") (pintype "passive"))
      (node (ref "U7") (pin "18") (pinfunction "18_18") (pintype "passive"))
      (node (ref "U7") (pin "19") (pinfunction "19_19") (pintype "passive"))
      (node (ref "U7") (pin "20") (pinfunction "20_20") (pintype "passive"))
      (node (ref "U7") (pin "21") (pinfunction "21_21") (pintype "passive"))
      (node (ref "U7") (pin "22") (pinfunction "22_22") (pintype "passive"))
      (node (ref "U7") (pin "23") (pinfunction "23_23") (pintype "passive"))
      (node (ref "U7") (pin "24") (pinfunction "24_24") (pintype "passive"))
      (node (ref "U7") (pin "25") (pinfunction "25_25") (pintype "passive"))
      (node (ref "U7") (pin "26") (pinfunction "26_26") (pintype "passive"))
      (node (ref "U7") (pin "27") (pinfunction "27_27") (pintype "passive"))
      (node (ref "U7") (pin "28") (pinfunction "28_28") (pintype "passive"))
      (node (ref "VT1") (pin "3") (pinfunction "3_3") (pintype "passive"))
    )
    (net (code "56") (name "/Valves_EN") (class "Default")
      (node (ref "J6") (pin "20") (pinfunction "20_20") (pintype "passive"))
      (node (ref "R3") (pin "1") (pinfunction "1_1") (pintype "passive"))
    )
    (net (code "57") (name "Net-(C9-Pad2)") (class "Default")
      (node (ref "C9") (pin "2") (pinfunction "2_2") (pintype "passive"))
      (node (ref "J6") (pin "11") (pinfunction "11_11") (pintype "passive"))
      (node (ref "R10") (pin "1") (pinfunction "1_1") (pintype "passive"))
      (node (ref "R11") (pin "1") (pinfunction "1_1") (pintype "passive"))
    )
    (net (code "58") (name "Net-(D1-A)") (class "Default")
      (node (ref "D1") (pin "1") (pinfunction "A_1") (pintype "passive"))
      (node (ref "R1") (pin "2") (pinfunction "2_2") (pintype "passive"))
    )
    (net (code "59") (name "Net-(D2-K)") (class "Default")
      (node (ref "D2") (pin "2") (pinfunction "K_2") (pintype "passive"))
      (node (ref "VT1") (pin "2") (pinfunction "2_2") (pintype "passive"))
    )
    (net (code "60") (name "Net-(D4-A)") (class "Default")
      (node (ref "D4") (pin "1") (pinfunction "A_1") (pintype "passive"))
      (node (ref "R2") (pin "1") (pinfunction "1_1") (pintype "passive"))
    )
    (net (code "61") (name "Net-(D5-K)") (class "Default")
      (node (ref "D5") (pin "2") (pinfunction "K_2") (pintype "passive"))
      (node (ref "R5") (pin "2") (pinfunction "2_2") (pintype "passive"))
      (node (ref "VT1") (pin "1") (pinfunction "G_1") (pintype "passive"))
    )
    (net (code "62") (name "Net-(D6-K)") (class "Default")
      (node (ref "C7") (pin "1") (pinfunction "1_1") (pintype "passive"))
      (node (ref "D6") (pin "2") (pinfunction "K_2") (pintype "passive"))
      (node (ref "U4") (pin "8") (pinfunction "Vb_8") (pintype "passive"))
    )
    (net (code "63") (name "Net-(U1-Gate)") (class "Default")
      (node (ref "R5") (pin "1") (pinfunction "1_1") (pintype "passive"))
      (node (ref "U1") (pin "6") (pinfunction "Gate_6") (pintype "passive"))
    )
    (net (code "64") (name "Net-(U1-IN)") (class "Default")
      (node (ref "R3") (pin "2") (pinfunction "2_2") (pintype "passive"))
      (node (ref "U1") (pin "1") (pinfunction "IN_1") (pintype "passive"))
    )
    (net (code "65") (name "Net-(U1-Out)") (class "Default")
      (node (ref "C1") (pin "1") (pinfunction "1_1") (pintype "passive"))
      (node (ref "U1") (pin "8") (pinfunction "Out_8") (pintype "passive"))
    )
    (net (code "66") (name "Net-(U1-RS)") (class "Default")
      (node (ref "R4") (pin "2") (pinfunction "2_2") (pintype "passive"))
      (node (ref "U1") (pin "3") (pinfunction "RS_3") (pintype "passive"))
    )
    (net (code "67") (name "Net-(U1-SW)") (class "Default")
      (node (ref "L3") (pin "1") (pinfunction "1_1") (pintype "passive"))
      (node (ref "U1") (pin "4") (pinfunction "SW_4") (pintype "passive"))
    )
    (net (code "68") (name "Net-(U4-HO)") (class "Default")
      (node (ref "R6") (pin "1") (pinfunction "1_1") (pintype "passive"))
      (node (ref "U4") (pin "7") (pinfunction "HO_7") (pintype "passive"))
    )
    (net (code "69") (name "Net-(U4-IN)") (class "Default")
      (node (ref "R7") (pin "2") (pinfunction "2_2") (pintype "passive"))
      (node (ref "U4") (pin "1") (pinfunction "IN_1") (pintype "passive"))
    )
    (net (code "70") (name "Net-(U4-LO)") (class "Default")
      (node (ref "R9") (pin "1") (pinfunction "1_1") (pintype "passive"))
      (node (ref "U4") (pin "4") (pinfunction "LO_4") (pintype "passive"))
    )
    (net (code "71") (name "Net-(U4-SD')") (class "Default")
      (node (ref "R8") (pin "2") (pinfunction "2_2") (pintype "passive"))
      (node (ref "U4") (pin "2") (pinfunction "SD'_2") (pintype "passive"))
    )
    (net (code "72") (name "Net-(VT2-G)") (class "Default")
      (node (ref "R6") (pin "2") (pinfunction "2_2") (pintype "passive"))
      (node (ref "VT2") (pin "1") (pinfunction "G_1") (pintype "passive"))
    )
    (net (code "73") (name "Net-(VT3-G)") (class "Default")
      (node (ref "R9") (pin "2") (pinfunction "2_2") (pintype "passive"))
      (node (ref "VT3") (pin "1") (pinfunction "G_1") (pintype "passive"))
    )
    (net (code "74") (name "P_GND") (class "Default")
      (node (ref "C2") (pin "1") (pinfunction "1_1") (pintype "passive"))
      (node (ref "C24") (pin "2") (pinfunction "2_2") (pintype "passive"))
      (node (ref "C25") (pin "1") (pinfunction "1_1") (pintype "passive"))
      (node (ref "C26") (pin "1") (pinfunction "1_1") (pintype "passive"))
      (node (ref "C27") (pin "1") (pinfunction "1_1") (pintype "passive"))
      (node (ref "C28") (pin "1") (pinfunction "1_1") (pintype "passive"))
      (node (ref "C29") (pin "1") (pinfunction "1_1") (pintype "passive"))
      (node (ref "C3") (pin "2") (pinfunction "2_2") (pintype "passive"))
      (node (ref "C30") (pin "1") (pinfunction "1_1") (pintype "passive"))
      (node (ref "C31") (pin "1") (pinfunction "1_1") (pintype "passive"))
      (node (ref "C32") (pin "2") (pinfunction "2_2") (pintype "passive"))
      (node (ref "C33") (pin "2") (pinfunction "2_2") (pintype "passive"))
      (node (ref "C34") (pin "1") (pinfunction "1_1") (pintype "passive"))
      (node (ref "C35") (pin "2") (pinfunction "2_2") (pintype "passive"))
      (node (ref "C36") (pin "1") (pinfunction "1_1") (pintype "passive"))
      (node (ref "C37") (pin "1") (pinfunction "1_1") (pintype "passive"))
      (node (ref "C4") (pin "2") (pinfunction "2_2") (pintype "passive"))
      (node (ref "C5") (pin "2") (pinfunction "2_2") (pintype "passive"))
      (node (ref "C6") (pin "2") (pinfunction "2_2") (pintype "passive"))
      (node (ref "C8") (pin "2") (pinfunction "2_2") (pintype "passive"))
      (node (ref "C9") (pin "1") (pinfunction "1_1") (pintype "passive"))
      (node (ref "D1") (pin "2") (pinfunction "K_2") (pintype "passive"))
      (node (ref "D3") (pin "1") (pinfunction "A_1") (pintype "passive"))
      (node (ref "D4") (pin "2") (pinfunction "K_2") (pintype "passive"))
      (node (ref "J3") (pin "1") (pinfunction "1_1") (pintype "passive"))
      (node (ref "J4") (pin "1") (pinfunction "1_1") (pintype "passive"))
      (node (ref "J6") (pin "12") (pinfunction "12_12") (pintype "passive"))
      (node (ref "J6") (pin "9") (pinfunction "9_9") (pintype "passive"))
      (node (ref "J7") (pin "1") (pinfunction "1_1") (pintype "passive"))
      (node (ref "J7") (pin "10") (pinfunction "10_10") (pintype "passive"))
      (node (ref "J7") (pin "11") (pinfunction "11_11") (pintype "passive"))
      (node (ref "J7") (pin "12") (pinfunction "12_12") (pintype "passive"))
      (node (ref "J7") (pin "13") (pinfunction "13_13") (pintype "passive"))
      (node (ref "J7") (pin "14") (pinfunction "14_14") (pintype "passive"))
      (node (ref "J7") (pin "15") (pinfunction "15_15") (pintype "passive"))
      (node (ref "J7") (pin "16") (pinfunction "16_16") (pintype "passive"))
      (node (ref "J7") (pin "17") (pinfunction "17_17") (pintype "passive"))
      (node (ref "J7") (pin "18") (pinfunction "18_18") (pintype "passive"))
      (node (ref "J7") (pin "19") (pinfunction "19_19") (pintype "passive"))
      (node (ref "J7") (pin "2") (pinfunction "2_2") (pintype "passive"))
      (node (ref "J7") (pin "20") (pinfunction "20_20") (pintype "passive"))
      (node (ref "J7") (pin "3") (pinfunction "3_3") (pintype "passive"))
      (node (ref "J7") (pin "4") (pinfunction "4_4") (pintype "passive"))
      (node (ref "J7") (pin "5") (pinfunction "5_5") (pintype "passive"))
      (node (ref "J7") (pin "6") (pinfunction "6_6") (pintype "passive"))
      (node (ref "J7") (pin "7") (pinfunction "7_7") (pintype "passive"))
      (node (ref "J7") (pin "8") (pinfunction "8_8") (pintype "passive"))
      (node (ref "J7") (pin "9") (pinfunction "9_9") (pintype "passive"))
      (node (ref "L1") (pin "2") (pinfunction "2_2") (pintype "passive"))
      (node (ref "L2") (pin "2") (pinfunction "2_2") (pintype "passive"))
      (node (ref "L4") (pin "2") (pinfunction "2_2") (pintype "passive"))
      (node (ref "L5") (pin "2") (pinfunction "2_2") (pintype "passive"))
      (node (ref "R11") (pin "2") (pinfunction "2_2") (pintype "passive"))
      (node (ref "R4") (pin "1") (pinfunction "1_1") (pintype "passive"))
      (node (ref "U1") (pin "2") (pinfunction "GND_2") (pintype "passive"))
      (node (ref "U2") (pin "1") (pinfunction "N.C._1") (pintype "passive"))
      (node (ref "U2") (pin "16") (pinfunction "PGND4_16") (pintype "passive"))
      (node (ref "U2") (pin "17") (pinfunction "PGND4_17") (pintype "passive"))
      (node (ref "U2") (pin "18") (pinfunction "N.C._18") (pintype "passive"))
      (node (ref "U2") (pin "19") (pinfunction "N.C._19") (pintype "passive"))
      (node (ref "U2") (pin "2") (pinfunction "PGND3_2") (pintype "passive"))
      (node (ref "U2") (pin "25") (pinfunction "PGND2_25") (pintype "passive"))
      (node (ref "U2") (pin "26") (pinfunction "PGND2_26") (pintype "passive"))
      (node (ref "U2") (pin "3") (pinfunction "PGND3_3") (pintype "passive"))
      (node (ref "U2") (pin "30") (pinfunction "PGND1_30") (pintype "passive"))
      (node (ref "U2") (pin "31") (pinfunction "PGND1_31") (pintype "passive"))
      (node (ref "U2") (pin "36") (pinfunction "N.C._36") (pintype "passive"))
      (node (ref "U3") (pin "1") (pinfunction "N.C._1") (pintype "passive"))
      (node (ref "U3") (pin "16") (pinfunction "PGND4_16") (pintype "passive"))
      (node (ref "U3") (pin "17") (pinfunction "PGND4_17") (pintype "passive"))
      (node (ref "U3") (pin "18") (pinfunction "N.C._18") (pintype "passive"))
      (node (ref "U3") (pin "19") (pinfunction "N.C._19") (pintype "passive"))
      (node (ref "U3") (pin "2") (pinfunction "PGND3_2") (pintype "passive"))
      (node (ref "U3") (pin "25") (pinfunction "PGND2_25") (pintype "passive"))
      (node (ref "U3") (pin "26") (pinfunction "PGND2_26") (pintype "passive"))
      (node (ref "U3") (pin "3") (pinfunction "PGND3_3") (pintype "passive"))
      (node (ref "U3") (pin "30") (pinfunction "PGND1_30") (pintype "passive"))
      (node (ref "U3") (pin "31") (pinfunction "PGND1_31") (pintype "passive"))
      (node (ref "U3") (pin "36") (pinfunction "N.C._36") (pintype "passive"))
      (node (ref "U4") (pin "3") (pinfunction "COM_3") (pintype "passive"))
      (node (ref "U5") (pin "1") (pinfunction "N.C._1") (pintype "passive"))
      (node (ref "U5") (pin "16") (pinfunction "PGND4_16") (pintype "passive"))
      (node (ref "U5") (pin "17") (pinfunction "PGND4_17") (pintype "passive"))
      (node (ref "U5") (pin "18") (pinfunction "N.C._18") (pintype "passive"))
      (node (ref "U5") (pin "19") (pinfunction "N.C._19") (pintype "passive"))
      (node (ref "U5") (pin "2") (pinfunction "PGND3_2") (pintype "passive"))
      (node (ref "U5") (pin "25") (pinfunction "PGND2_25") (pintype "passive"))
      (node (ref "U5") (pin "26") (pinfunction "PGND2_26") (pintype "passive"))
      (node (ref "U5") (pin "3") (pinfunction "PGND3_3") (pintype "passive"))
      (node (ref "U5") (pin "30") (pinfunction "PGND1_30") (pintype "passive"))
      (node (ref "U5") (pin "31") (pinfunction "PGND1_31") (pintype "passive"))
      (node (ref "U5") (pin "36") (pinfunction "N.C._36") (pintype "passive"))
      (node (ref "U6") (pin "1") (pinfunction "N.C._1") (pintype "passive"))
      (node (ref "U6") (pin "16") (pinfunction "PGND4_16") (pintype "passive"))
      (node (ref "U6") (pin "17") (pinfunction "PGND4_17") (pintype "passive"))
      (node (ref "U6") (pin "18") (pinfunction "N.C._18") (pintype "passive"))
      (node (ref "U6") (pin "19") (pinfunction "N.C._19") (pintype "passive"))
      (node (ref "U6") (pin "2") (pinfunction "PGND3_2") (pintype "passive"))
      (node (ref "U6") (pin "25") (pinfunction "PGND2_25") (pintype "passive"))
      (node (ref "U6") (pin "26") (pinfunction "PGND2_26") (pintype "passive"))
      (node (ref "U6") (pin "3") (pinfunction "PGND3_3") (pintype "passive"))
      (node (ref "U6") (pin "30") (pinfunction "PGND1_30") (pintype "passive"))
      (node (ref "U6") (pin "31") (pinfunction "PGND1_31") (pintype "passive"))
      (node (ref "U6") (pin "36") (pinfunction "N.C._36") (pintype "passive"))
      (node (ref "U7") (pin "1") (pinfunction "1_1") (pintype "passive"))
      (node (ref "VT3") (pin "3") (pinfunction "3_3") (pintype "passive"))
    )
    (net (code "75") (name "unconnected-(J6-Pad4)") (class "Default")
      (node (ref "J6") (pin "4") (pinfunction "4_4") (pintype "passive"))
    )
    (net (code "76") (name "unconnected-(J6-Pad10)") (class "Default")
      (node (ref "J6") (pin "10") (pinfunction "10_10") (pintype "passive"))
    )
    (net (code "77") (name "unconnected-(U2-N.C.-Pad29)") (class "Default")
      (node (ref "U2") (pin "29") (pinfunction "N.C._29") (pintype "passive"))
    )
    (net (code "78") (name "unconnected-(U3-D3-Pad6)") (class "Default")
      (node (ref "U3") (pin "6") (pinfunction "D3_6") (pintype "output+no_connect"))
    )
    (net (code "79") (name "unconnected-(U3-D3-Pad7)") (class "Default")
      (node (ref "U3") (pin "7") (pinfunction "D3_7") (pintype "output+no_connect"))
    )
    (net (code "80") (name "unconnected-(U3-IN3-Pad33)") (class "Default")
      (node (ref "U3") (pin "33") (pinfunction "IN3_33") (pintype "passive+no_connect"))
    )
    (net (code "81") (name "unconnected-(U3-N.C.-Pad29)") (class "Default")
      (node (ref "U3") (pin "29") (pinfunction "N.C._29") (pintype "passive"))
    )
    (net (code "82") (name "unconnected-(U3-Q3-Pad4)") (class "Default")
      (node (ref "U3") (pin "4") (pinfunction "Q3_4") (pintype "input+no_connect"))
    )
    (net (code "83") (name "unconnected-(U3-Q3-Pad5)") (class "Default")
      (node (ref "U3") (pin "5") (pinfunction "Q3_5") (pintype "input+no_connect"))
    )
    (net (code "84") (name "unconnected-(U3-ST3-Pad35)") (class "Default")
      (node (ref "U3") (pin "35") (pinfunction "ST3_35") (pintype "passive+no_connect"))
    )
    (net (code "85") (name "unconnected-(U5-IN2-Pad21)") (class "Default")
      (node (ref "U5") (pin "21") (pinfunction "IN2_21") (pintype "passive+no_connect"))
    )
    (net (code "86") (name "unconnected-(U5-N.C.-Pad29)") (class "Default")
      (node (ref "U5") (pin "29") (pinfunction "N.C._29") (pintype "passive"))
    )
    (net (code "87") (name "unconnected-(U5-Q2-Pad10)") (class "Default")
      (node (ref "U5") (pin "10") (pinfunction "Q2_10") (pintype "input+no_connect"))
    )
    (net (code "88") (name "unconnected-(U5-Q2-Pad11)") (class "Default")
      (node (ref "U5") (pin "11") (pinfunction "Q2_11") (pintype "input+no_connect"))
    )
    (net (code "89") (name "unconnected-(U5-ST2-Pad23)") (class "Default")
      (node (ref "U5") (pin "23") (pinfunction "ST2_23") (pintype "passive+no_connect"))
    )
    (net (code "90") (name "unconnected-(U6-N.C.-Pad29)") (class "Default")
      (node (ref "U6") (pin "29") (pinfunction "N.C._29") (pintype "passive"))
    )
  )
)
